# ESP.net
KiCad netlist of a schematic drawn in EAGLE
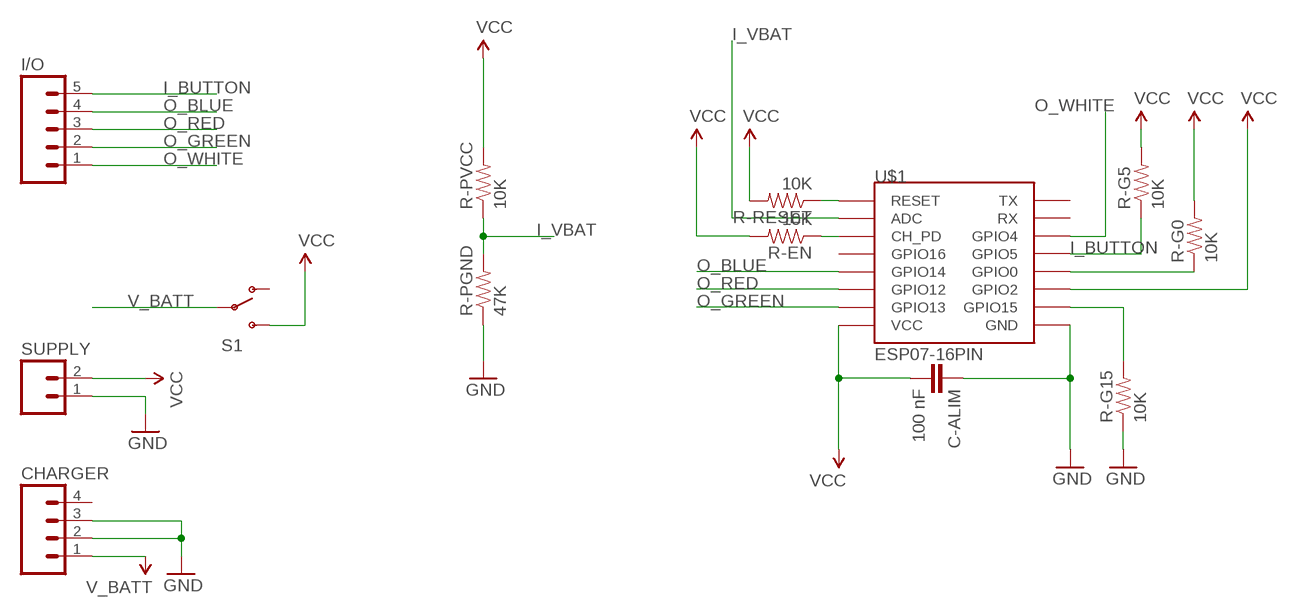
[diagram p0: schematic, sheet 1]

(export (version "E")
  (design (tool "Eeschema 10.0.6"))
  (components
    (comp (ref "C-ALIM")
      (value "100 nF")
      (footprint "eagle-import:0805")
      (libsource (lib "eagle-import") (part "CAP0805"))
    )
    (comp (ref "CHARGER")
      (value "M04NO_SILK_ALL_ROUND")
      (footprint "eagle-import:1X04_NO_SILK_ALL_ROUND")
      (libsource (lib "eagle-import") (part "M04NO_SILK_ALL_ROUND"))
    )
    (comp (ref "I/O")
      (value "M05NO_SILK")
      (footprint "eagle-import:1X05_NO_SILK")
      (libsource (lib "eagle-import") (part "M05NO_SILK"))
    )
    (comp (ref "R-EN")
      (value "10K")
      (footprint "eagle-import:0805")
      (libsource (lib "eagle-import") (part "RESISTOR0805-RES"))
    )
    (comp (ref "R-G0")
      (value "10K")
      (footprint "eagle-import:0805")
      (libsource (lib "eagle-import") (part "RESISTOR0805-RES"))
    )
    (comp (ref "R-G5")
      (value "10K")
      (footprint "eagle-import:0805")
      (libsource (lib "eagle-import") (part "RESISTOR0805-RES"))
    )
    (comp (ref "R-G15")
      (value "10K")
      (footprint "eagle-import:0805")
      (libsource (lib "eagle-import") (part "RESISTOR0805-RES"))
    )
    (comp (ref "R-PGND")
      (value "47K")
      (footprint "eagle-import:0805")
      (libsource (lib "eagle-import") (part "RESISTOR0805-RES"))
    )
    (comp (ref "R-PVCC")
      (value "10K")
      (footprint "eagle-import:0805")
      (libsource (lib "eagle-import") (part "RESISTOR0805-RES"))
    )
    (comp (ref "R-RESET")
      (value "10K")
      (footprint "eagle-import:0805")
      (libsource (lib "eagle-import") (part "RESISTOR0805-RES"))
    )
    (comp (ref "S1")
      (value "SWITCH-SPDTSMD2")
      (footprint "eagle-import:SWITCH-SPDT-SMD")
      (libsource (lib "eagle-import") (part "SWITCH-SPDTSMD2"))
    )
    (comp (ref "SUPPLY")
      (value "M021X02_NO_SILK")
      (footprint "eagle-import:1X02_NO_SILK")
      (libsource (lib "eagle-import") (part "M021X02_NO_SILK"))
    )
    (comp (ref "U$1")
      (value "ESP07-16PIN")
      (footprint "eagle-import:ESP07-16PIN")
      (libsource (lib "eagle-import") (part "ESP07-16PIN"))
    )
  )
  (nets
    (net (code "1") (name "/I_BUTTON") (class "Default")
      (node (ref "I/O") (pin "5") (pinfunction "5_5") (pintype "passive"))
      (node (ref "R-G5") (pin "1") (pinfunction "1_1") (pintype "passive"))
      (node (ref "U$1") (pin "GPIO5") (pinfunction "GPIO5_GPIO5") (pintype "bidirectional"))
    )
    (net (code "2") (name "/I_VBAT") (class "Default")
      (node (ref "R-PGND") (pin "2") (pinfunction "2_2") (pintype "passive"))
      (node (ref "R-PVCC") (pin "1") (pinfunction "1_1") (pintype "passive"))
      (node (ref "U$1") (pin "ADC") (pinfunction "ADC_ADC") (pintype "bidirectional"))
    )
    (net (code "3") (name "/O_BLUE") (class "Default")
      (node (ref "I/O") (pin "4") (pinfunction "4_4") (pintype "passive"))
      (node (ref "U$1") (pin "GPIO14") (pinfunction "GPIO14_GPIO14") (pintype "bidirectional"))
    )
    (net (code "4") (name "/O_GREEN") (class "Default")
      (node (ref "I/O") (pin "2") (pinfunction "2_2") (pintype "passive"))
      (node (ref "U$1") (pin "GPIO13") (pinfunction "GPIO13_GPIO13") (pintype "bidirectional"))
    )
    (net (code "5") (name "/O_RED") (class "Default")
      (node (ref "I/O") (pin "3") (pinfunction "3_3") (pintype "passive"))
      (node (ref "U$1") (pin "GPIO12") (pinfunction "GPIO12_GPIO12") (pintype "bidirectional"))
    )
    (net (code "6") (name "/O_WHITE") (class "Default")
      (node (ref "I/O") (pin "1") (pinfunction "1_1") (pintype "passive"))
      (node (ref "U$1") (pin "GPIO4") (pinfunction "GPIO4_GPIO4") (pintype "bidirectional"))
    )
    (net (code "7") (name "GND") (class "Default")
      (node (ref "C-ALIM") (pin "1") (pinfunction "1_1") (pintype "passive"))
      (node (ref "CHARGER") (pin "2") (pinfunction "2_2") (pintype "passive"))
      (node (ref "CHARGER") (pin "3") (pinfunction "3_3") (pintype "passive"))
      (node (ref "R-G15") (pin "1") (pinfunction "1_1") (pintype "passive"))
      (node (ref "R-PGND") (pin "1") (pinfunction "1_1") (pintype "passive"))
      (node (ref "SUPPLY") (pin "1") (pinfunction "1_1") (pintype "passive"))
      (node (ref "U$1") (pin "GND") (pinfunction "GND_GND") (pintype "bidirectional"))
    )
    (net (code "8") (name "Net-(R-EN-Pad1)") (class "Default")
      (node (ref "R-EN") (pin "1") (pinfunction "1_1") (pintype "passive"))
      (node (ref "U$1") (pin "CH_PD") (pinfunction "CH_PD_CH_PD") (pintype "bidirectional"))
    )
    (net (code "9") (name "Net-(R-G0-Pad1)") (class "Default")
      (node (ref "R-G0") (pin "1") (pinfunction "1_1") (pintype "passive"))
      (node (ref "U$1") (pin "GPIO0") (pinfunction "GPIO0_GPIO0") (pintype "bidirectional"))
    )
    (net (code "10") (name "Net-(R-G15-Pad2)") (class "Default")
      (node (ref "R-G15") (pin "2") (pinfunction "2_2") (pintype "passive"))
      (node (ref "U$1") (pin "GPIO15") (pinfunction "GPIO15_GPIO15") (pintype "bidirectional"))
    )
    (net (code "11") (name "Net-(U$1-RESET)") (class "Default")
      (node (ref "R-RESET") (pin "1") (pinfunction "1_1") (pintype "passive"))
      (node (ref "U$1") (pin "REST") (pinfunction "RESET_REST") (pintype "bidirectional"))
    )
    (net (code "12") (name "VCC") (class "Default")
      (node (ref "C-ALIM") (pin "2") (pinfunction "2_2") (pintype "passive"))
      (node (ref "R-EN") (pin "2") (pinfunction "2_2") (pintype "passive"))
      (node (ref "R-G0") (pin "2") (pinfunction "2_2") (pintype "passive"))
      (node (ref "R-G5") (pin "2") (pinfunction "2_2") (pintype "passive"))
      (node (ref "R-PVCC") (pin "2") (pinfunction "2_2") (pintype "passive"))
      (node (ref "R-RESET") (pin "2") (pinfunction "2_2") (pintype "passive"))
      (node (ref "S1") (pin "3") (pinfunction "S_3") (pintype "passive"))
      (node (ref "SUPPLY") (pin "2") (pinfunction "2_2") (pintype "passive"))
      (node (ref "U$1") (pin "GPIO2") (pinfunction "GPIO2_GPIO2") (pintype "bidirectional"))
      (node (ref "U$1") (pin "VCC") (pinfunction "VCC_VCC") (pintype "bidirectional"))
    )
    (net (code "13") (name "V_BATT") (class "Default")
      (node (ref "CHARGER") (pin "1") (pinfunction "1_1") (pintype "passive"))
      (node (ref "S1") (pin "2") (pinfunction "P_2") (pintype "passive"))
    )
    (net (code "14") (name "unconnected-(CHARGER-Pad4)") (class "Default")
      (node (ref "CHARGER") (pin "4") (pinfunction "4_4") (pintype "passive"))
    )
    (net (code "15") (name "unconnected-(S1-O-Pad1)") (class "Default")
      (node (ref "S1") (pin "1") (pinfunction "O_1") (pintype "passive"))
    )
    (net (code "16") (name "unconnected-(U$1-PadGPIO16)") (class "Default")
      (node (ref "U$1") (pin "GPIO16") (pinfunction "GPIO16_GPIO16") (pintype "bidirectional"))
    )
    (net (code "17") (name "unconnected-(U$1-PadRX)") (class "Default")
      (node (ref "U$1") (pin "RX") (pinfunction "RX_RX") (pintype "bidirectional"))
    )
    (net (code "18") (name "unconnected-(U$1-PadTX)") (class "Default")
      (node (ref "U$1") (pin "TX") (pinfunction "TX_TX") (pintype "bidirectional"))
    )
  )
)
